# Sony_PSP_USB-C.net
KiCad netlist of a schematic drawn in EAGLE
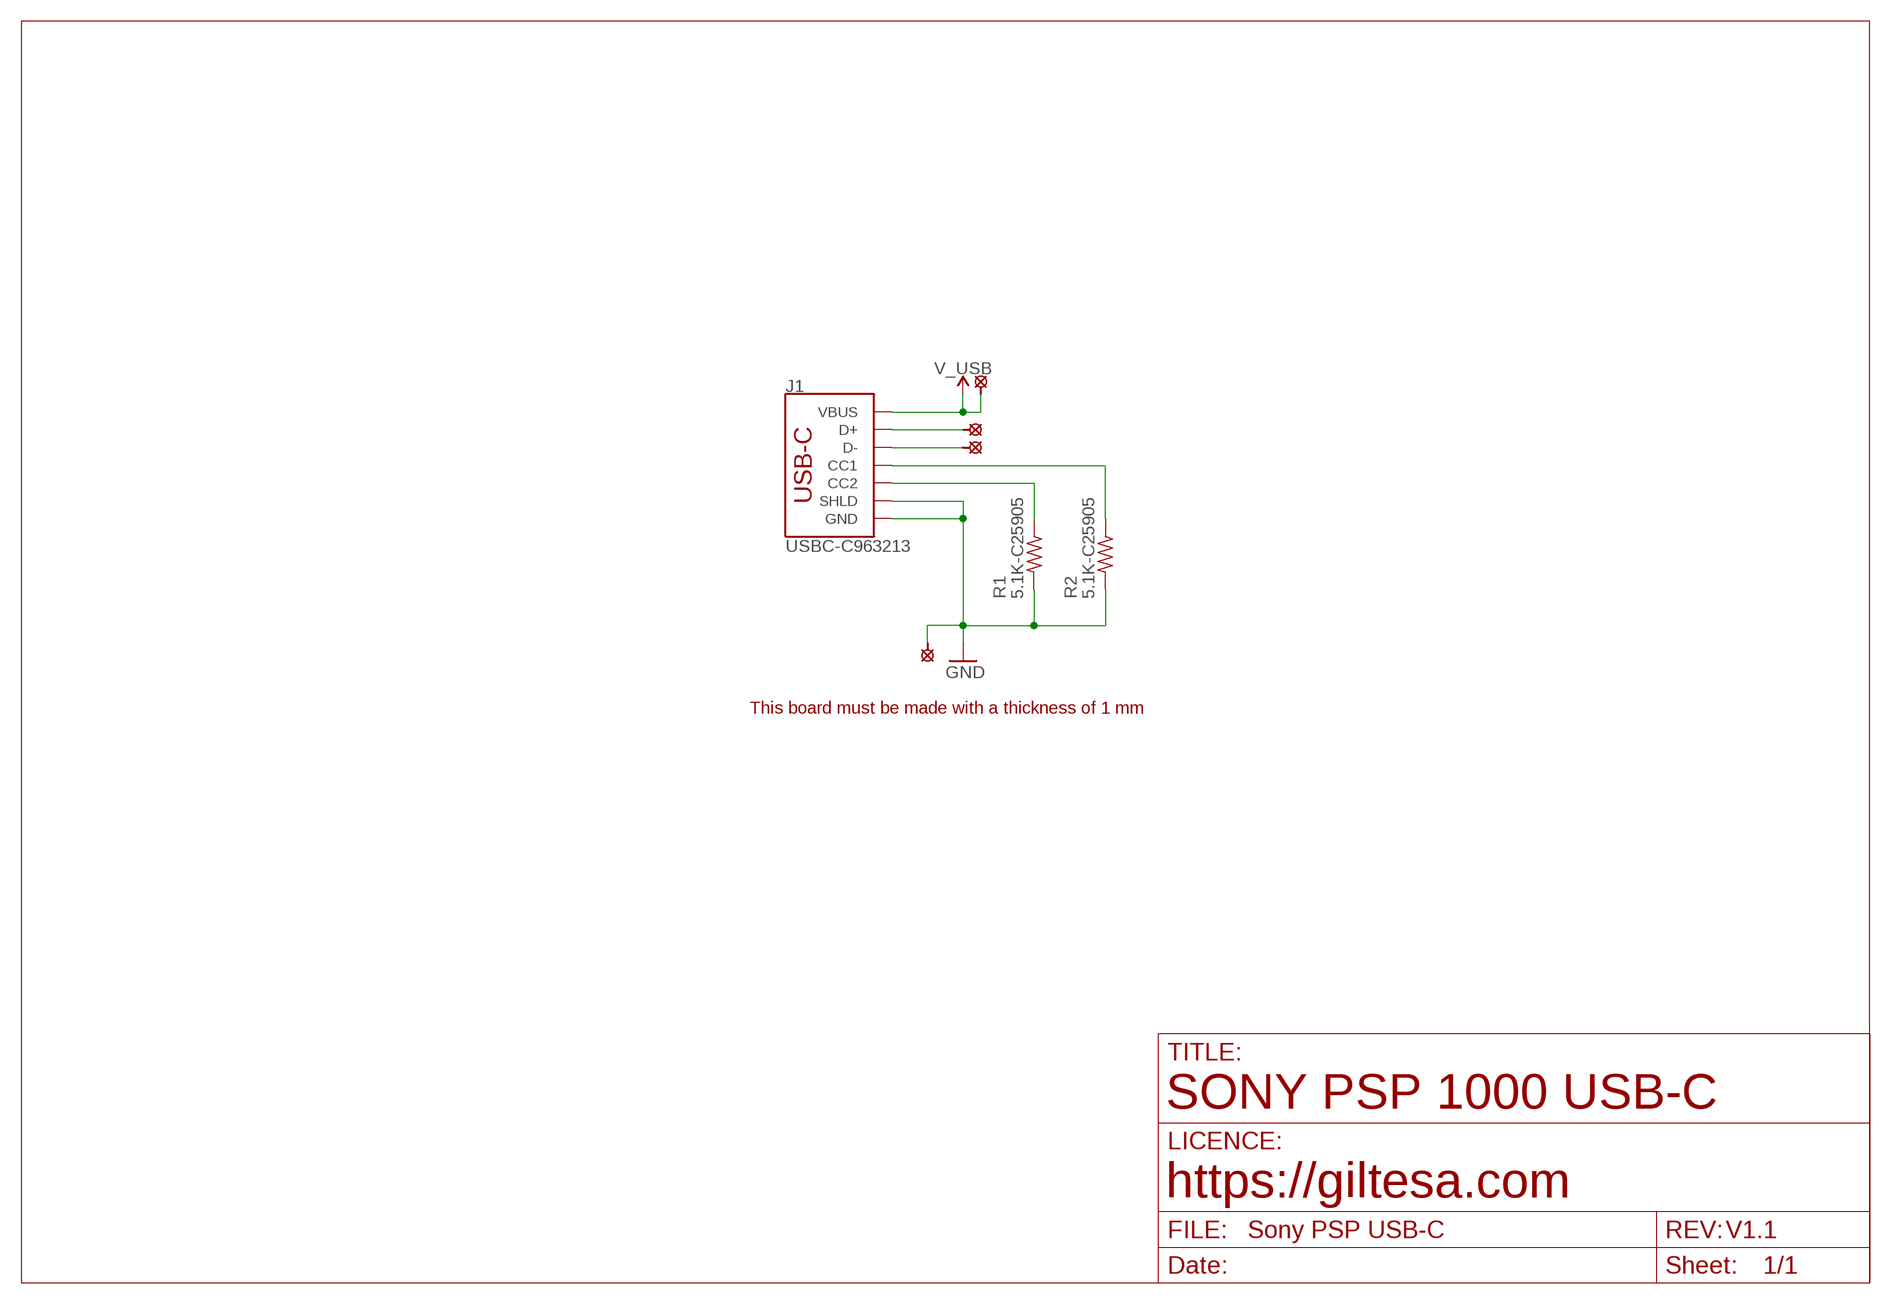
[diagram p0: schematic, sheet 1]

(export (version "E")
  (design (tool "Eeschema 10.0.6"))
  (components
    (comp (ref "J1")
      (value "USBC-C963213")
      (footprint "eagle-import:USB-C_18P_SLIM_GT-USB-7025")
      (libsource (lib "eagle-import") (part "USB-C_16P_DATA_SLIM"))
    )
    (comp (ref "R1")
      (value "5.1K-C25905")
      (footprint "eagle-import:R0402")
      (libsource (lib "eagle-import") (part "R0402"))
    )
    (comp (ref "R2")
      (value "5.1K-C25905")
      (footprint "eagle-import:R0402")
      (libsource (lib "eagle-import") (part "R0402"))
    )
    (comp (ref "U$1")
      (value "SOLDER_PAD_PSP_1000")
      (footprint "eagle-import:PSP_1000_PAD")
      (libsource (lib "eagle-import") (part "SOLDER_PAD_PSP_1000"))
    )
    (comp (ref "U$3")
      (value "SOLDER_PAD_PSP_1000")
      (footprint "eagle-import:PSP_1000_PAD")
      (libsource (lib "eagle-import") (part "SOLDER_PAD_PSP_1000"))
    )
    (comp (ref "U$5")
      (value "SOLDER_PAD-1.2")
      (footprint "eagle-import:SOLDER_PAD_1.2")
      (libsource (lib "eagle-import") (part "SOLDER_PAD-1.2"))
    )
    (comp (ref "U$6")
      (value "SOLDER_PAD-1.2")
      (footprint "eagle-import:SOLDER_PAD_1.2")
      (libsource (lib "eagle-import") (part "SOLDER_PAD-1.2"))
    )
  )
  (nets
    (net (code "1") (name "GND") (class "Default")
      (node (ref "J1") (pin "A1-GND") (pinfunction "GND_A1-GND") (pintype "bidirectional"))
      (node (ref "J1") (pin "A12-GND") (pinfunction "GND_A12-GND") (pintype "bidirectional"))
      (node (ref "J1") (pin "B1-GND") (pinfunction "GND_B1-GND") (pintype "bidirectional"))
      (node (ref "J1") (pin "B12-GND") (pinfunction "GND_B12-GND") (pintype "bidirectional"))
      (node (ref "J1") (pin "GND1") (pinfunction "GND_GND1") (pintype "bidirectional"))
      (node (ref "J1") (pin "GND2") (pinfunction "GND_GND2") (pintype "bidirectional"))
      (node (ref "J1") (pin "SHLD1") (pinfunction "SHLD_SHLD1") (pintype "bidirectional"))
      (node (ref "J1") (pin "SHLD2") (pinfunction "SHLD_SHLD2") (pintype "bidirectional"))
      (node (ref "J1") (pin "SHLD3") (pinfunction "SHLD_SHLD3") (pintype "bidirectional"))
      (node (ref "J1") (pin "SHLD4") (pinfunction "SHLD_SHLD4") (pintype "bidirectional"))
      (node (ref "R1") (pin "2") (pinfunction "2_2") (pintype "passive"))
      (node (ref "R2") (pin "2") (pinfunction "2_2") (pintype "passive"))
      (node (ref "U$1") (pin "1") (pinfunction "P$1_1") (pintype "bidirectional"))
    )
    (net (code "2") (name "Net-(J1-CC1)") (class "Default")
      (node (ref "J1") (pin "A5-CC1") (pinfunction "CC1_A5-CC1") (pintype "bidirectional"))
      (node (ref "R2") (pin "1") (pinfunction "1_1") (pintype "passive"))
    )
    (net (code "3") (name "Net-(J1-CC2)") (class "Default")
      (node (ref "J1") (pin "B5-CC2") (pinfunction "CC2_B5-CC2") (pintype "bidirectional"))
      (node (ref "R1") (pin "1") (pinfunction "1_1") (pintype "passive"))
    )
    (net (code "4") (name "Net-(J1-D+-PadA6-DP1)") (class "Default")
      (node (ref "J1") (pin "A6-DP1") (pinfunction "D+_A6-DP1") (pintype "bidirectional"))
      (node (ref "J1") (pin "B6-DP2") (pinfunction "D+_B6-DP2") (pintype "bidirectional"))
      (node (ref "U$5") (pin "P$1") (pinfunction "P$1_P$1") (pintype "bidirectional"))
    )
    (net (code "5") (name "Net-(J1-D--PadA7-DN1)") (class "Default")
      (node (ref "J1") (pin "A7-DN1") (pinfunction "D-_A7-DN1") (pintype "bidirectional"))
      (node (ref "J1") (pin "B7-DN2") (pinfunction "D-_B7-DN2") (pintype "bidirectional"))
      (node (ref "U$6") (pin "P$1") (pinfunction "P$1_P$1") (pintype "bidirectional"))
    )
    (net (code "6") (name "V_USB") (class "Default")
      (node (ref "J1") (pin "A4-VBUS") (pinfunction "VBUS_A4-VBUS") (pintype "bidirectional"))
      (node (ref "J1") (pin "A9-VBUS") (pinfunction "VBUS_A9-VBUS") (pintype "bidirectional"))
      (node (ref "J1") (pin "B4-VBUS") (pinfunction "VBUS_B4-VBUS") (pintype "bidirectional"))
      (node (ref "J1") (pin "B9-VBUS") (pinfunction "VBUS_B9-VBUS") (pintype "bidirectional"))
      (node (ref "U$3") (pin "1") (pinfunction "P$1_1") (pintype "bidirectional"))
    )
  )
)
